# Signal_Connectors.net
KiCad netlist of a schematic drawn in Altium Designer
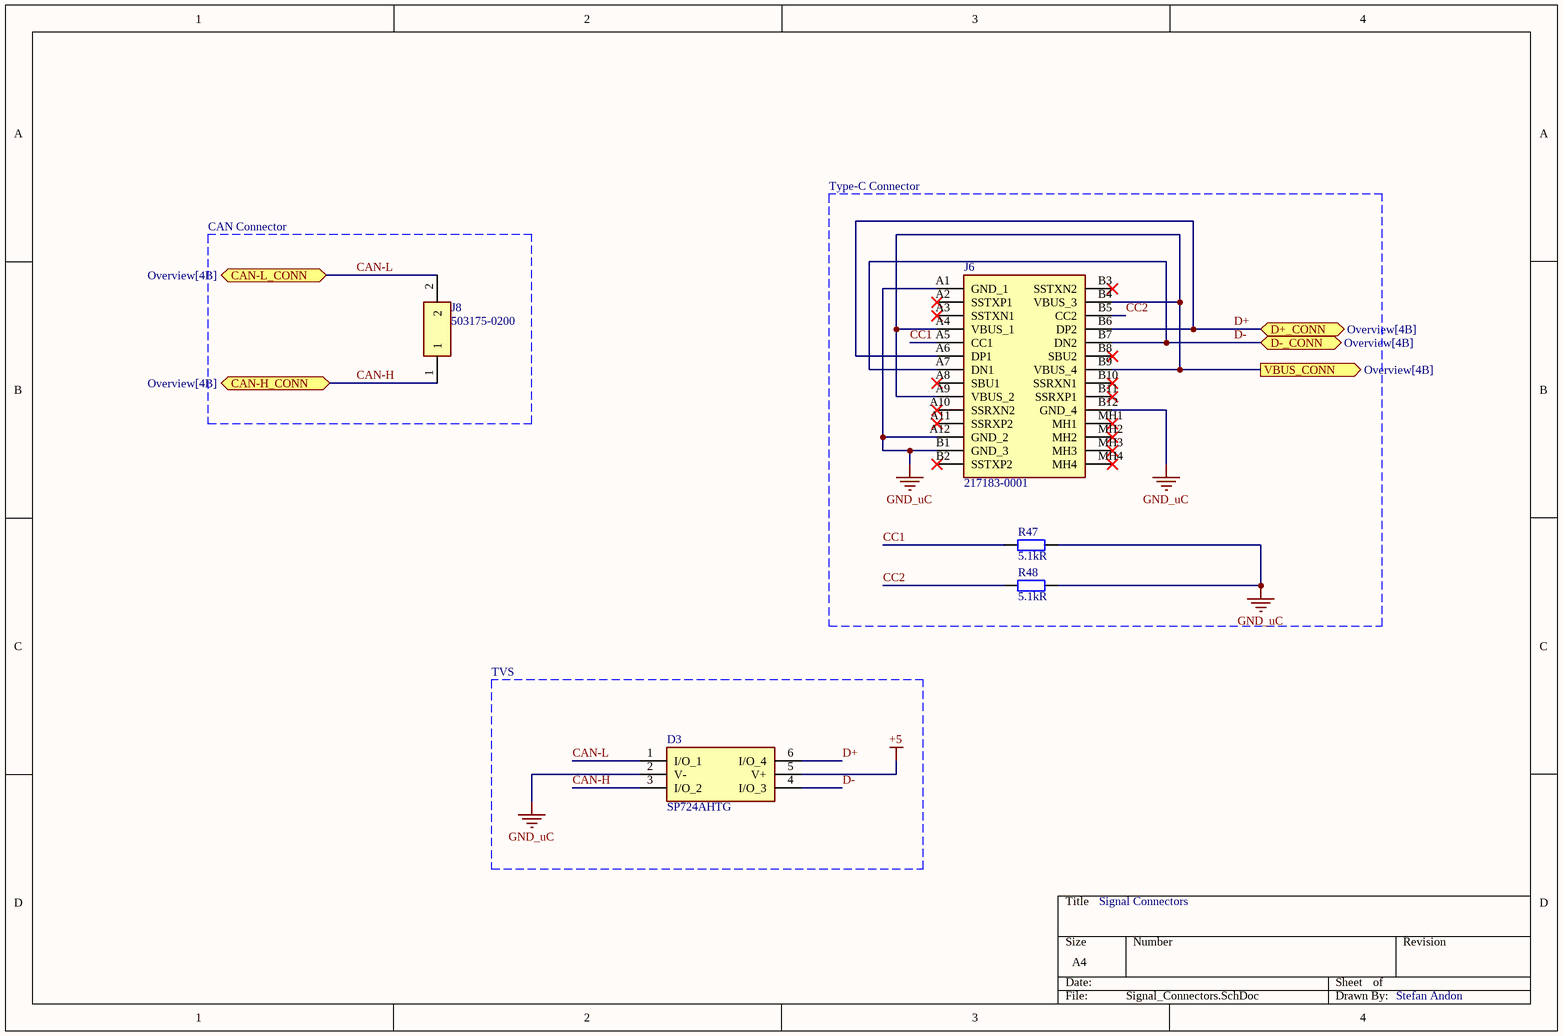
[diagram p0: Signal_Connectors.SchDoc]

(export (version "E")
  (design (tool "Eeschema 10.0.6"))
  (components
    (comp (ref "D3")
      (value "SP724AHTG")
      (footprint "SamacSys:SOT95P280X145-6N")
      (description "TVS Diode (Bi-directional)")
      (fields (field (name "MOUSER PART NUMBER") "576-SP724AHTG"))
      (libsource (lib "*") (part "SP724AHTG"))
    )
    (comp (ref "J6")
      (value "217183-0001")
      (footprint "SamacSys:2171830001")
      (description "Connector")
      (fields (field (name "MOUSER PART NUMBER") "538-217183-0001"))
      (libsource (lib "*") (part "217183-0001"))
    )
    (comp (ref "J8")
      (value "503175-0200")
      (footprint "SamacSys:5031750200")
      (description "Connector")
      (fields (field (name "MOUSER PART NUMBER") "538-503175-0200"))
      (libsource (lib "*") (part "503175-0200"))
    )
    (comp (ref "R47")
      (value "5.1kR")
      (footprint "RES_0603")
      (fields
        (field (name "TOLERANCE") "tbd")
        (field (name "POWER") "7W")
        (field (name "Comment") "Resistor_SMD")
      )
      (libsource (lib "TUfast e") (part "Resistor"))
    )
    (comp (ref "R48")
      (value "5.1kR")
      (footprint "RES_0603")
      (fields
        (field (name "TOLERANCE") "tbd")
        (field (name "POWER") "7W")
        (field (name "Comment") "Resistor_SMD")
      )
      (libsource (lib "TUfast e") (part "Resistor"))
    )
  )
  (nets
    (net (code "1") (name "+5") (class "Default")
      (node (ref "D3") (pin "5") (pinfunction "V+_5") (pintype "passive"))
    )
    (net (code "2") (name "/CAN-H") (class "Default")
      (node (ref "D3") (pin "3") (pinfunction "I/O_2_3") (pintype "passive"))
      (node (ref "J8") (pin "1") (pinfunction "1_1") (pintype "passive"))
    )
    (net (code "3") (name "/CAN-L") (class "Default")
      (node (ref "D3") (pin "1") (pinfunction "I/O_1_1") (pintype "passive"))
      (node (ref "J8") (pin "2") (pinfunction "2_2") (pintype "passive"))
    )
    (net (code "4") (name "/CC1") (class "Default")
      (node (ref "J6") (pin "A5") (pinfunction "CC1_A5") (pintype "passive"))
      (node (ref "R47") (pin "2") (pinfunction "2_2") (pintype "passive"))
    )
    (net (code "5") (name "/CC2") (class "Default")
      (node (ref "J6") (pin "B5") (pinfunction "CC2_B5") (pintype "passive"))
      (node (ref "R48") (pin "2") (pinfunction "2_2") (pintype "passive"))
    )
    (net (code "6") (name "/D+") (class "Default")
      (node (ref "D3") (pin "6") (pinfunction "I/O_4_6") (pintype "passive"))
      (node (ref "J6") (pin "A6") (pinfunction "DP1_A6") (pintype "passive"))
      (node (ref "J6") (pin "B6") (pinfunction "DP2_B6") (pintype "passive"))
    )
    (net (code "7") (name "/D-") (class "Default")
      (node (ref "D3") (pin "4") (pinfunction "I/O_3_4") (pintype "passive"))
      (node (ref "J6") (pin "A7") (pinfunction "DN1_A7") (pintype "passive"))
      (node (ref "J6") (pin "B7") (pinfunction "DN2_B7") (pintype "passive"))
    )
    (net (code "8") (name "/VBUS_CONN") (class "Default")
      (node (ref "J6") (pin "A4") (pinfunction "VBUS_1_A4") (pintype "passive"))
      (node (ref "J6") (pin "A9") (pinfunction "VBUS_2_A9") (pintype "passive"))
      (node (ref "J6") (pin "B4") (pinfunction "VBUS_3_B4") (pintype "passive"))
      (node (ref "J6") (pin "B9") (pinfunction "VBUS_4_B9") (pintype "passive"))
    )
    (net (code "9") (name "GND_uC") (class "Default")
      (node (ref "D3") (pin "2") (pinfunction "V-_2") (pintype "passive"))
      (node (ref "J6") (pin "A1") (pinfunction "GND_1_A1") (pintype "passive"))
      (node (ref "J6") (pin "A12") (pinfunction "GND_2_A12") (pintype "passive"))
      (node (ref "J6") (pin "B1") (pinfunction "GND_3_B1") (pintype "passive"))
      (node (ref "J6") (pin "B12") (pinfunction "GND_4_B12") (pintype "passive"))
      (node (ref "R47") (pin "1") (pinfunction "1_1") (pintype "passive"))
      (node (ref "R48") (pin "1") (pinfunction "1_1") (pintype "passive"))
    )
    (net (code "10") (name "unconnected-(J6-PadMH1)") (class "Default")
      (node (ref "J6") (pin "MH1") (pinfunction "MH1_MH1") (pintype "passive+no_connect"))
    )
    (net (code "11") (name "unconnected-(J6-PadMH2)") (class "Default")
      (node (ref "J6") (pin "MH2") (pinfunction "MH2_MH2") (pintype "passive+no_connect"))
    )
    (net (code "12") (name "unconnected-(J6-PadMH3)") (class "Default")
      (node (ref "J6") (pin "MH3") (pinfunction "MH3_MH3") (pintype "passive+no_connect"))
    )
    (net (code "13") (name "unconnected-(J6-PadMH4)") (class "Default")
      (node (ref "J6") (pin "MH4") (pinfunction "MH4_MH4") (pintype "passive+no_connect"))
    )
    (net (code "14") (name "unconnected-(J6-SBU1-PadA8)") (class "Default")
      (node (ref "J6") (pin "A8") (pinfunction "SBU1_A8") (pintype "passive+no_connect"))
    )
    (net (code "15") (name "unconnected-(J6-SBU2-PadB8)") (class "Default")
      (node (ref "J6") (pin "B8") (pinfunction "SBU2_B8") (pintype "passive+no_connect"))
    )
    (net (code "16") (name "unconnected-(J6-SSRXN1-PadB10)") (class "Default")
      (node (ref "J6") (pin "B10") (pinfunction "SSRXN1_B10") (pintype "passive+no_connect"))
    )
    (net (code "17") (name "unconnected-(J6-SSRXN2-PadA10)") (class "Default")
      (node (ref "J6") (pin "A10") (pinfunction "SSRXN2_A10") (pintype "passive+no_connect"))
    )
    (net (code "18") (name "unconnected-(J6-SSRXP1-PadB11)") (class "Default")
      (node (ref "J6") (pin "B11") (pinfunction "SSRXP1_B11") (pintype "passive+no_connect"))
    )
    (net (code "19") (name "unconnected-(J6-SSRXP2-PadA11)") (class "Default")
      (node (ref "J6") (pin "A11") (pinfunction "SSRXP2_A11") (pintype "passive+no_connect"))
    )
    (net (code "20") (name "unconnected-(J6-SSTXN1-PadA3)") (class "Default")
      (node (ref "J6") (pin "A3") (pinfunction "SSTXN1_A3") (pintype "passive+no_connect"))
    )
    (net (code "21") (name "unconnected-(J6-SSTXN2-PadB3)") (class "Default")
      (node (ref "J6") (pin "B3") (pinfunction "SSTXN2_B3") (pintype "passive+no_connect"))
    )
    (net (code "22") (name "unconnected-(J6-SSTXP1-PadA2)") (class "Default")
      (node (ref "J6") (pin "A2") (pinfunction "SSTXP1_A2") (pintype "passive+no_connect"))
    )
    (net (code "23") (name "unconnected-(J6-SSTXP2-PadB2)") (class "Default")
      (node (ref "J6") (pin "B2") (pinfunction "SSTXP2_B2") (pintype "passive+no_connect"))
    )
  )
)
